# Power.net
KiCad netlist of a schematic drawn in Altium Designer
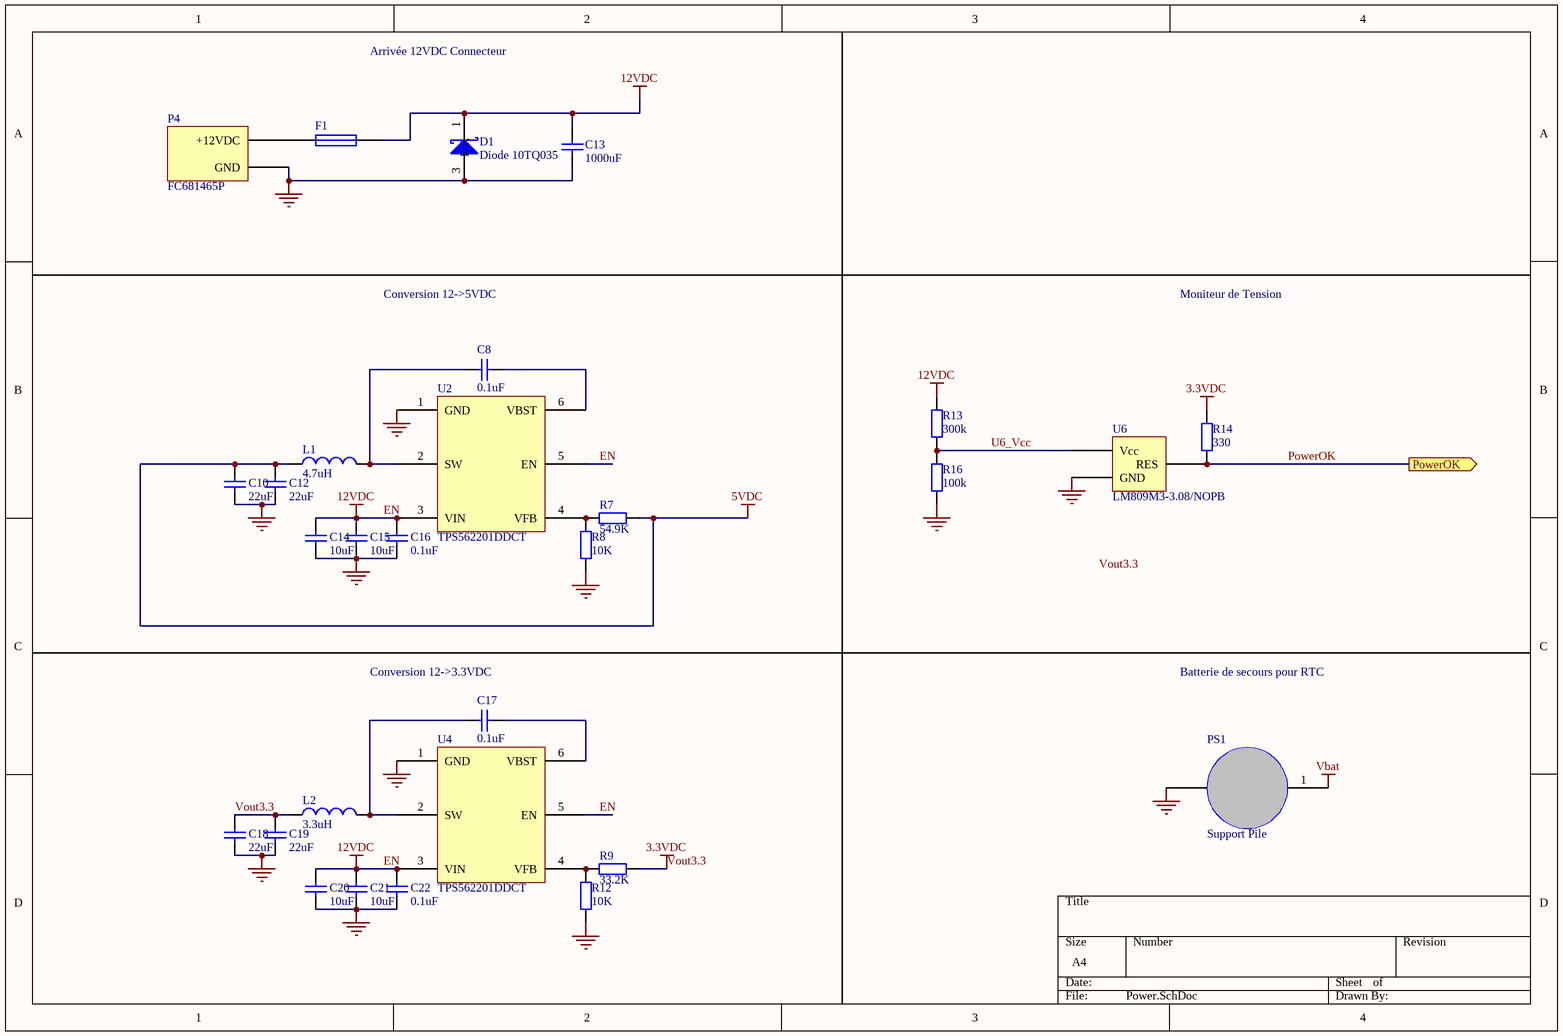
[diagram p0: Power.SchDoc]

(export (version "E")
  (design (tool "Eeschema 10.0.6"))
  (components
    (comp (ref "C8")
      (value "0.1uF")
      (footprint "0603")
      (description "Reg_5v")
      (libsource (lib "Miscellaneous Devices") (part "Cap"))
    )
    (comp (ref "C10")
      (value "22uF")
      (footprint "0603")
      (description "Reg_5v")
      (libsource (lib "Miscellaneous Devices") (part "Cap"))
    )
    (comp (ref "C12")
      (value "22uF")
      (footprint "0603")
      (description "Reg_5v")
      (libsource (lib "Miscellaneous Devices") (part "Cap"))
    )
    (comp (ref "C13")
      (value "1000uF")
      (footprint "Condo_trav")
      (description "Capacitor")
      (libsource (lib "Miscellaneous Devices") (part "Cap"))
    )
    (comp (ref "C14")
      (value "10uF")
      (footprint "0603")
      (description "Reg_5v")
      (libsource (lib "Miscellaneous Devices") (part "Cap"))
    )
    (comp (ref "C15")
      (value "10uF")
      (footprint "0603")
      (description "Reg_5v")
      (libsource (lib "Miscellaneous Devices") (part "Cap"))
    )
    (comp (ref "C16")
      (value "0.1uF")
      (footprint "0603")
      (description "Reg_5v")
      (libsource (lib "Miscellaneous Devices") (part "Cap"))
    )
    (comp (ref "C17")
      (value "0.1uF")
      (footprint "0603")
      (description "Reg_5v")
      (libsource (lib "Miscellaneous Devices") (part "Cap"))
    )
    (comp (ref "C18")
      (value "22uF")
      (footprint "0603")
      (description "Reg_5v")
      (libsource (lib "Miscellaneous Devices") (part "Cap"))
    )
    (comp (ref "C19")
      (value "22uF")
      (footprint "0603")
      (description "Reg_5v")
      (libsource (lib "Miscellaneous Devices") (part "Cap"))
    )
    (comp (ref "C20")
      (value "10uF")
      (footprint "0603")
      (description "Reg_5v")
      (libsource (lib "Miscellaneous Devices") (part "Cap"))
    )
    (comp (ref "C21")
      (value "10uF")
      (footprint "0603")
      (description "Reg_5v")
      (libsource (lib "Miscellaneous Devices") (part "Cap"))
    )
    (comp (ref "C22")
      (value "0.1uF")
      (footprint "0603")
      (description "Reg_5v")
      (libsource (lib "Miscellaneous Devices") (part "Cap"))
    )
    (comp (ref "D1")
      (value "Diode 10TQ035")
      (footprint "DiodeZin")
      (description "Diode Zenner")
      (libsource (lib "Miscellaneous Devices") (part "Diode 10TQ035"))
    )
    (comp (ref "F1")
      (value "Fuse 1")
      (footprint "FUSIBLE")
      (description "Fuse")
      (libsource (lib "Miscellaneous Devices") (part "Fuse 1"))
    )
    (comp (ref "L1")
      (value "4.7uH")
      (footprint "Bobine Traversante 4.7")
      (description "L_Reg_5v")
      (libsource (lib "Miscellaneous Devices") (part "Inductor"))
    )
    (comp (ref "L2")
      (value "3.3uH")
      (footprint "Bobine Traversante 4.7")
      (description "L_Reg_3v")
      (libsource (lib "Miscellaneous Devices") (part "Inductor"))
    )
    (comp (ref "P4")
      (value "FC681465P")
      (footprint "JackAlim")
      (description "Power connector")
      (libsource (lib "Schlib1") (part "FC68148S"))
    )
    (comp (ref "PS1")
      (value "Support Pile")
      (footprint "Pile")
      (libsource (lib "Schlib1") (part "SMTU-1225-1-LF"))
    )
    (comp (ref "R7")
      (value "54.9K")
      (footprint "0603")
      (description "Resistor")
      (libsource (lib "Miscellaneous Devices") (part "Res2"))
    )
    (comp (ref "R8")
      (value "10K")
      (footprint "0603")
      (description "Resistor")
      (libsource (lib "") (part "Res2_1"))
    )
    (comp (ref "R9")
      (value "33.2K")
      (footprint "0603")
      (description "Resistor")
      (libsource (lib "Miscellaneous Devices") (part "Res2"))
    )
    (comp (ref "R12")
      (value "10K")
      (footprint "0603")
      (description "Resistor")
      (libsource (lib "") (part "Res2_1"))
    )
    (comp (ref "R13")
      (value "300k")
      (footprint "0603")
      (description "Resistor")
      (libsource (lib "") (part "Res2_1"))
    )
    (comp (ref "R14")
      (value "330")
      (footprint "0603")
      (description "Resistor")
      (libsource (lib "") (part "Res2_1"))
    )
    (comp (ref "R16")
      (value "100k")
      (footprint "0603")
      (description "Resistor")
      (libsource (lib "") (part "Res2_1"))
    )
    (comp (ref "U2")
      (value "TPS562201DDCT")
      (footprint "TPS562201DDCT")
      (description "Reg 12V-5V")
      (libsource (lib "Schlib1") (part "TPS562201DDCT"))
    )
    (comp (ref "U4")
      (value "TPS562201DDCT")
      (footprint "TPS562201DDCT")
      (description "Reg 12V-5V")
      (libsource (lib "Schlib1") (part "TPS562201DDCT"))
    )
    (comp (ref "U6")
      (value "LM809M3-3.08/NOPB")
      (footprint "LM809")
      (description "Voltage Monitor")
      (libsource (lib "Schlib1") (part "LM809M3-3.08/NOPB"))
    )
  )
  (nets
    (net (code "1") (name "/PowerOK") (class "Default")
      (node (ref "R14") (pin "1") (pinfunction "1_1") (pintype "passive"))
      (node (ref "U6") (pin "2") (pinfunction "RES_2") (pintype "passive"))
    )
    (net (code "2") (name "/U6_Vcc") (class "Default")
      (node (ref "R13") (pin "1") (pinfunction "1_1") (pintype "passive"))
      (node (ref "R16") (pin "2") (pinfunction "2_2") (pintype "passive"))
      (node (ref "U6") (pin "3") (pinfunction "Vcc_3") (pintype "passive"))
    )
    (net (code "3") (name "3.3VDC") (class "Default")
      (node (ref "C18") (pin "1") (pinfunction "1_1") (pintype "passive"))
      (node (ref "C19") (pin "1") (pinfunction "1_1") (pintype "passive"))
      (node (ref "L2") (pin "1") (pinfunction "1_1") (pintype "passive"))
      (node (ref "R14") (pin "2") (pinfunction "2_2") (pintype "passive"))
      (node (ref "R9") (pin "1") (pinfunction "1_1") (pintype "passive"))
    )
    (net (code "4") (name "5VDC") (class "Default")
      (node (ref "C10") (pin "1") (pinfunction "1_1") (pintype "passive"))
      (node (ref "C12") (pin "1") (pinfunction "1_1") (pintype "passive"))
      (node (ref "L1") (pin "1") (pinfunction "1_1") (pintype "passive"))
      (node (ref "R7") (pin "1") (pinfunction "1_1") (pintype "passive"))
    )
    (net (code "5") (name "12VDC") (class "Default")
      (node (ref "C13") (pin "2") (pinfunction "2_2") (pintype "passive"))
      (node (ref "C14") (pin "1") (pinfunction "1_1") (pintype "passive"))
      (node (ref "C15") (pin "1") (pinfunction "1_1") (pintype "passive"))
      (node (ref "C16") (pin "1") (pinfunction "1_1") (pintype "passive"))
      (node (ref "C20") (pin "1") (pinfunction "1_1") (pintype "passive"))
      (node (ref "C21") (pin "1") (pinfunction "1_1") (pintype "passive"))
      (node (ref "C22") (pin "1") (pinfunction "1_1") (pintype "passive"))
      (node (ref "D1") (pin "1") (pinfunction "K_1") (pintype "passive"))
      (node (ref "F1") (pin "2") (pinfunction "2_2") (pintype "passive"))
      (node (ref "R13") (pin "2") (pinfunction "2_2") (pintype "passive"))
      (node (ref "U2") (pin "3") (pinfunction "VIN_3") (pintype "passive"))
      (node (ref "U2") (pin "5") (pinfunction "EN_5") (pintype "passive"))
      (node (ref "U4") (pin "3") (pinfunction "VIN_3") (pintype "passive"))
      (node (ref "U4") (pin "5") (pinfunction "EN_5") (pintype "passive"))
    )
    (net (code "6") (name "GND") (class "Default")
      (node (ref "C10") (pin "2") (pinfunction "2_2") (pintype "passive"))
      (node (ref "C12") (pin "2") (pinfunction "2_2") (pintype "passive"))
      (node (ref "C13") (pin "1") (pinfunction "1_1") (pintype "passive"))
      (node (ref "C14") (pin "2") (pinfunction "2_2") (pintype "passive"))
      (node (ref "C15") (pin "2") (pinfunction "2_2") (pintype "passive"))
      (node (ref "C16") (pin "2") (pinfunction "2_2") (pintype "passive"))
      (node (ref "C18") (pin "2") (pinfunction "2_2") (pintype "passive"))
      (node (ref "C19") (pin "2") (pinfunction "2_2") (pintype "passive"))
      (node (ref "C20") (pin "2") (pinfunction "2_2") (pintype "passive"))
      (node (ref "C21") (pin "2") (pinfunction "2_2") (pintype "passive"))
      (node (ref "C22") (pin "2") (pinfunction "2_2") (pintype "passive"))
      (node (ref "D1") (pin "3") (pinfunction "A_3") (pintype "passive"))
      (node (ref "P4") (pin "3") (pinfunction "GND_3") (pintype "passive"))
      (node (ref "PS1") (pin "2") (pinfunction "-_2") (pintype "passive"))
      (node (ref "R12") (pin "1") (pinfunction "1_1") (pintype "passive"))
      (node (ref "R16") (pin "1") (pinfunction "1_1") (pintype "passive"))
      (node (ref "R8") (pin "1") (pinfunction "1_1") (pintype "passive"))
      (node (ref "U2") (pin "1") (pinfunction "GND_1") (pintype "passive"))
      (node (ref "U4") (pin "1") (pinfunction "GND_1") (pintype "passive"))
      (node (ref "U6") (pin "1") (pinfunction "GND_1") (pintype "passive"))
    )
    (net (code "7") (name "Net-(P4-+12VDC)") (class "Default")
      (node (ref "F1") (pin "1") (pinfunction "1_1") (pintype "passive"))
      (node (ref "P4") (pin "1") (pinfunction "+12VDC_1") (pintype "passive"))
    )
    (net (code "8") (name "Net-(U2-SW)") (class "Default")
      (node (ref "C8") (pin "1") (pinfunction "1_1") (pintype "passive"))
      (node (ref "L1") (pin "2") (pinfunction "2_2") (pintype "passive"))
      (node (ref "U2") (pin "2") (pinfunction "SW_2") (pintype "passive"))
    )
    (net (code "9") (name "Net-(U2-VBST)") (class "Default")
      (node (ref "C8") (pin "2") (pinfunction "2_2") (pintype "passive"))
      (node (ref "U2") (pin "6") (pinfunction "VBST_6") (pintype "passive"))
    )
    (net (code "10") (name "Net-(U2-VFB)") (class "Default")
      (node (ref "R7") (pin "2") (pinfunction "2_2") (pintype "passive"))
      (node (ref "R8") (pin "2") (pinfunction "2_2") (pintype "passive"))
      (node (ref "U2") (pin "4") (pinfunction "VFB_4") (pintype "passive"))
    )
    (net (code "11") (name "Net-(U4-SW)") (class "Default")
      (node (ref "C17") (pin "1") (pinfunction "1_1") (pintype "passive"))
      (node (ref "L2") (pin "2") (pinfunction "2_2") (pintype "passive"))
      (node (ref "U4") (pin "2") (pinfunction "SW_2") (pintype "passive"))
    )
    (net (code "12") (name "Net-(U4-VBST)") (class "Default")
      (node (ref "C17") (pin "2") (pinfunction "2_2") (pintype "passive"))
      (node (ref "U4") (pin "6") (pinfunction "VBST_6") (pintype "passive"))
    )
    (net (code "13") (name "Net-(U4-VFB)") (class "Default")
      (node (ref "R12") (pin "2") (pinfunction "2_2") (pintype "passive"))
      (node (ref "R9") (pin "2") (pinfunction "2_2") (pintype "passive"))
      (node (ref "U4") (pin "4") (pinfunction "VFB_4") (pintype "passive"))
    )
    (net (code "14") (name "Vbat") (class "Default")
      (node (ref "PS1") (pin "1") (pinfunction "+_1") (pintype "passive"))
    )
    (net (code "15") (name "unconnected-(P4-GND-Pad2)") (class "Default")
      (node (ref "P4") (pin "2") (pinfunction "GND_2") (pintype "passive"))
    )
  )
)
